# Quad-Thermocouple-Shield.net
KiCad netlist of a schematic drawn in EAGLE
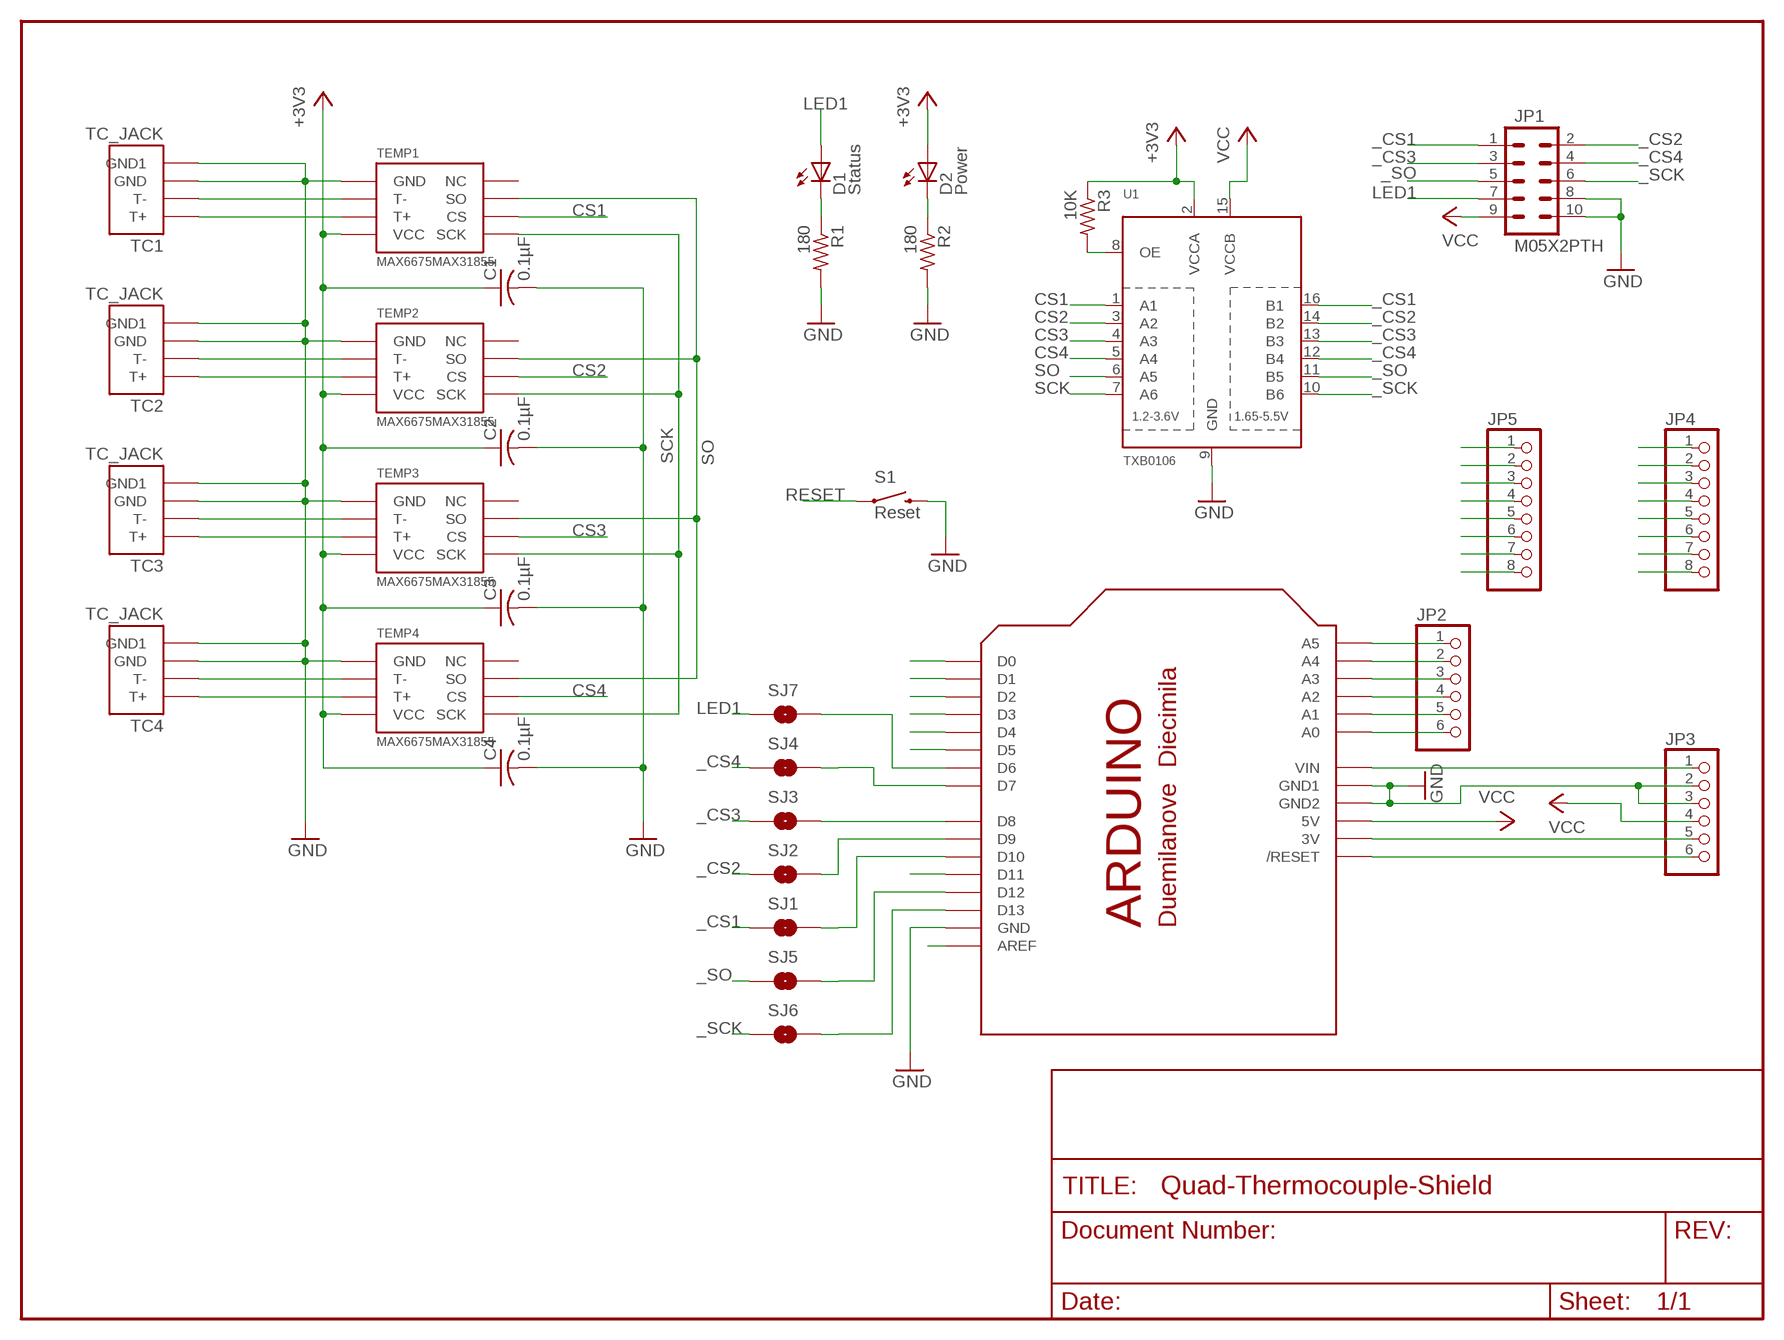
[diagram p0: schematic, sheet 1]

(export (version "E")
  (design (tool "Eeschema 10.0.6"))
  (components
    (comp (ref "C1")
      (value "0.1µF")
      (footprint "eagle-import:C0603")
      (libsource (lib "eagle-import") (part "C-USC0603"))
    )
    (comp (ref "C2")
      (value "0.1µF")
      (footprint "eagle-import:C0603")
      (libsource (lib "eagle-import") (part "C-USC0603"))
    )
    (comp (ref "C3")
      (value "0.1µF")
      (footprint "eagle-import:C0603")
      (libsource (lib "eagle-import") (part "C-USC0603"))
    )
    (comp (ref "C4")
      (value "0.1µF")
      (footprint "eagle-import:C0603")
      (libsource (lib "eagle-import") (part "C-USC0603"))
    )
    (comp (ref "D1")
      (value "Status")
      (footprint "eagle-import:CHIPLED_0805")
      (libsource (lib "eagle-import") (part "LEDCHIPLED_0805"))
    )
    (comp (ref "D2")
      (value "Power")
      (footprint "eagle-import:CHIPLED_0805")
      (libsource (lib "eagle-import") (part "LEDCHIPLED_0805"))
    )
    (comp (ref "JP1")
      (value "M05X2PTH")
      (footprint "eagle-import:AVR_ICSP")
      (libsource (lib "eagle-import") (part "M05X2PTH"))
    )
    (comp (ref "JP2")
      (value "PINHD-1X6CB")
      (footprint "eagle-import:1X06-CLEANBIG")
      (libsource (lib "eagle-import") (part "PINHD-1X6CB"))
    )
    (comp (ref "JP3")
      (value "PINHD-1X6CB")
      (footprint "eagle-import:1X06-CLEANBIG")
      (libsource (lib "eagle-import") (part "PINHD-1X6CB"))
    )
    (comp (ref "JP4")
      (value "PINHD-1X8CLEANBIG")
      (footprint "eagle-import:1X08-CLEANBIG")
      (libsource (lib "eagle-import") (part "PINHD-1X8CLEANBIG"))
    )
    (comp (ref "JP5")
      (value "PINHD-1X8CLEANBIG")
      (footprint "eagle-import:1X08-CLEANBIG")
      (libsource (lib "eagle-import") (part "PINHD-1X8CLEANBIG"))
    )
    (comp (ref "R1")
      (value "180")
      (footprint "eagle-import:R0603")
      (libsource (lib "eagle-import") (part "R-US_R0603"))
    )
    (comp (ref "R2")
      (value "180")
      (footprint "eagle-import:R0603")
      (libsource (lib "eagle-import") (part "R-US_R0603"))
    )
    (comp (ref "R3")
      (value "10K")
      (footprint "eagle-import:R0603")
      (libsource (lib "eagle-import") (part "R-US_R0603"))
    )
    (comp (ref "S1")
      (value "Reset")
      (footprint "eagle-import:TACTILE_SWITCH_SMD")
      (libsource (lib "eagle-import") (part "SWITCH-MOMENTARY-2SMD"))
    )
    (comp (ref "SJ1")
      (value "SOLDERJUMPERTRACE")
      (footprint "eagle-import:SJ_2S-TRACE")
      (libsource (lib "eagle-import") (part "SOLDERJUMPERTRACE"))
    )
    (comp (ref "SJ2")
      (value "SOLDERJUMPERTRACE")
      (footprint "eagle-import:SJ_2S-TRACE")
      (libsource (lib "eagle-import") (part "SOLDERJUMPERTRACE"))
    )
    (comp (ref "SJ3")
      (value "SOLDERJUMPERTRACE")
      (footprint "eagle-import:SJ_2S-TRACE")
      (libsource (lib "eagle-import") (part "SOLDERJUMPERTRACE"))
    )
    (comp (ref "SJ4")
      (value "SOLDERJUMPERTRACE")
      (footprint "eagle-import:SJ_2S-TRACE")
      (libsource (lib "eagle-import") (part "SOLDERJUMPERTRACE"))
    )
    (comp (ref "SJ5")
      (value "SOLDERJUMPERTRACE")
      (footprint "eagle-import:SJ_2S-TRACE")
      (libsource (lib "eagle-import") (part "SOLDERJUMPERTRACE"))
    )
    (comp (ref "SJ6")
      (value "SOLDERJUMPERTRACE")
      (footprint "eagle-import:SJ_2S-TRACE")
      (libsource (lib "eagle-import") (part "SOLDERJUMPERTRACE"))
    )
    (comp (ref "SJ7")
      (value "SOLDERJUMPERTRACE")
      (footprint "eagle-import:SJ_2S-TRACE")
      (libsource (lib "eagle-import") (part "SOLDERJUMPERTRACE"))
    )
    (comp (ref "TC1")
      (value "TC_JACK")
      (footprint "eagle-import:TC_JACK")
      (libsource (lib "eagle-import") (part "TC_JACK"))
    )
    (comp (ref "TC2")
      (value "TC_JACK")
      (footprint "eagle-import:TC_JACK")
      (libsource (lib "eagle-import") (part "TC_JACK"))
    )
    (comp (ref "TC3")
      (value "TC_JACK")
      (footprint "eagle-import:TC_JACK")
      (libsource (lib "eagle-import") (part "TC_JACK"))
    )
    (comp (ref "TC4")
      (value "TC_JACK")
      (footprint "eagle-import:TC_JACK")
      (libsource (lib "eagle-import") (part "TC_JACK"))
    )
    (comp (ref "TEMP1")
      (value "MAX6675MAX31855")
      (footprint "eagle-import:SOIC-8")
      (libsource (lib "eagle-import") (part "MAX6675MAX31855"))
    )
    (comp (ref "TEMP2")
      (value "MAX6675MAX31855")
      (footprint "eagle-import:SOIC-8")
      (libsource (lib "eagle-import") (part "MAX6675MAX31855"))
    )
    (comp (ref "TEMP3")
      (value "MAX6675MAX31855")
      (footprint "eagle-import:SOIC-8")
      (libsource (lib "eagle-import") (part "MAX6675MAX31855"))
    )
    (comp (ref "TEMP4")
      (value "MAX6675MAX31855")
      (footprint "eagle-import:SOIC-8")
      (libsource (lib "eagle-import") (part "MAX6675MAX31855"))
    )
    (comp (ref "U$3")
      (value "ARDUINOUNO")
      (footprint "eagle-import:ARDUINO")
      (libsource (lib "eagle-import") (part "ARDUINOUNO"))
    )
    (comp (ref "U1")
      (value "TXB0106")
      (footprint "eagle-import:TSSOP16")
      (libsource (lib "eagle-import") (part "TXB0106PWR"))
    )
  )
  (nets
    (net (code "1") (name "+3V3") (class "Default")
      (node (ref "C1") (pin "1") (pinfunction "1_1") (pintype "passive"))
      (node (ref "C2") (pin "1") (pinfunction "1_1") (pintype "passive"))
      (node (ref "C3") (pin "1") (pinfunction "1_1") (pintype "passive"))
      (node (ref "C4") (pin "1") (pinfunction "1_1") (pintype "passive"))
      (node (ref "D2") (pin "A") (pinfunction "A_A") (pintype "passive"))
      (node (ref "JP3") (pin "5") (pinfunction "5_5") (pintype "passive"))
      (node (ref "R3") (pin "1") (pinfunction "1_1") (pintype "passive"))
      (node (ref "TEMP1") (pin "VCC") (pinfunction "VCC_VCC") (pintype "bidirectional"))
      (node (ref "TEMP2") (pin "VCC") (pinfunction "VCC_VCC") (pintype "bidirectional"))
      (node (ref "TEMP3") (pin "VCC") (pinfunction "VCC_VCC") (pintype "bidirectional"))
      (node (ref "TEMP4") (pin "VCC") (pinfunction "VCC_VCC") (pintype "bidirectional"))
      (node (ref "U$3") (pin "3V") (pinfunction "3V_3V") (pintype "power_in"))
      (node (ref "U1") (pin "2") (pinfunction "VCCA_2") (pintype "bidirectional"))
    )
    (net (code "2") (name "/AREF") (class "Default")
      (node (ref "JP4") (pin "8") (pinfunction "8_8") (pintype "passive"))
      (node (ref "U$3") (pin "AREF") (pinfunction "AREF_AREF") (pintype "bidirectional"))
    )
    (net (code "3") (name "/CS1") (class "Default")
      (node (ref "TEMP1") (pin "CS") (pinfunction "CS_CS") (pintype "bidirectional"))
      (node (ref "U1") (pin "1") (pinfunction "A1_1") (pintype "bidirectional"))
    )
    (net (code "4") (name "/CS2") (class "Default")
      (node (ref "TEMP2") (pin "CS") (pinfunction "CS_CS") (pintype "bidirectional"))
      (node (ref "U1") (pin "3") (pinfunction "A2_3") (pintype "bidirectional"))
    )
    (net (code "5") (name "/CS3") (class "Default")
      (node (ref "TEMP3") (pin "CS") (pinfunction "CS_CS") (pintype "bidirectional"))
      (node (ref "U1") (pin "4") (pinfunction "A3_4") (pintype "bidirectional"))
    )
    (net (code "6") (name "/CS4") (class "Default")
      (node (ref "TEMP4") (pin "CS") (pinfunction "CS_CS") (pintype "bidirectional"))
      (node (ref "U1") (pin "5") (pinfunction "A4_5") (pintype "bidirectional"))
    )
    (net (code "7") (name "/D0") (class "Default")
      (node (ref "JP5") (pin "1") (pinfunction "1_1") (pintype "passive"))
      (node (ref "U$3") (pin "D0") (pinfunction "D0_D0") (pintype "bidirectional"))
    )
    (net (code "8") (name "/D1") (class "Default")
      (node (ref "JP5") (pin "2") (pinfunction "2_2") (pintype "passive"))
      (node (ref "U$3") (pin "D1") (pinfunction "D1_D1") (pintype "bidirectional"))
    )
    (net (code "9") (name "/D2") (class "Default")
      (node (ref "JP5") (pin "3") (pinfunction "3_3") (pintype "passive"))
      (node (ref "U$3") (pin "D2") (pinfunction "D2_D2") (pintype "bidirectional"))
    )
    (net (code "10") (name "/D3") (class "Default")
      (node (ref "JP5") (pin "4") (pinfunction "4_4") (pintype "passive"))
      (node (ref "U$3") (pin "D3") (pinfunction "D3_D3") (pintype "bidirectional"))
    )
    (net (code "11") (name "/D4") (class "Default")
      (node (ref "JP5") (pin "5") (pinfunction "5_5") (pintype "passive"))
      (node (ref "U$3") (pin "D4") (pinfunction "D4_D4") (pintype "bidirectional"))
    )
    (net (code "12") (name "/D5") (class "Default")
      (node (ref "JP5") (pin "6") (pinfunction "6_6") (pintype "passive"))
      (node (ref "U$3") (pin "D5") (pinfunction "D5_D5") (pintype "bidirectional"))
    )
    (net (code "13") (name "/D6") (class "Default")
      (node (ref "JP5") (pin "7") (pinfunction "7_7") (pintype "passive"))
      (node (ref "SJ7") (pin "2") (pinfunction "2_2") (pintype "passive"))
      (node (ref "U$3") (pin "D6") (pinfunction "D6_D6") (pintype "bidirectional"))
    )
    (net (code "14") (name "/D7") (class "Default")
      (node (ref "JP5") (pin "8") (pinfunction "8_8") (pintype "passive"))
      (node (ref "SJ4") (pin "2") (pinfunction "2_2") (pintype "passive"))
      (node (ref "U$3") (pin "D7") (pinfunction "D7_D7") (pintype "bidirectional"))
    )
    (net (code "15") (name "/D8") (class "Default")
      (node (ref "JP4") (pin "1") (pinfunction "1_1") (pintype "passive"))
      (node (ref "SJ3") (pin "2") (pinfunction "2_2") (pintype "passive"))
      (node (ref "U$3") (pin "D8") (pinfunction "D8_D8") (pintype "bidirectional"))
    )
    (net (code "16") (name "/D9") (class "Default")
      (node (ref "JP4") (pin "2") (pinfunction "2_2") (pintype "passive"))
      (node (ref "SJ2") (pin "2") (pinfunction "2_2") (pintype "passive"))
      (node (ref "U$3") (pin "D9") (pinfunction "D9_D9") (pintype "bidirectional"))
    )
    (net (code "17") (name "/D10") (class "Default")
      (node (ref "JP4") (pin "3") (pinfunction "3_3") (pintype "passive"))
      (node (ref "SJ1") (pin "2") (pinfunction "2_2") (pintype "passive"))
      (node (ref "U$3") (pin "D10") (pinfunction "D10_D10") (pintype "bidirectional"))
    )
    (net (code "18") (name "/D11") (class "Default")
      (node (ref "JP4") (pin "4") (pinfunction "4_4") (pintype "passive"))
      (node (ref "U$3") (pin "D11") (pinfunction "D11_D11") (pintype "bidirectional"))
    )
    (net (code "19") (name "/D12") (class "Default")
      (node (ref "JP4") (pin "5") (pinfunction "5_5") (pintype "passive"))
      (node (ref "SJ5") (pin "2") (pinfunction "2_2") (pintype "passive"))
      (node (ref "U$3") (pin "D12") (pinfunction "D12_D12") (pintype "bidirectional"))
    )
    (net (code "20") (name "/D13") (class "Default")
      (node (ref "JP4") (pin "6") (pinfunction "6_6") (pintype "passive"))
      (node (ref "SJ6") (pin "2") (pinfunction "2_2") (pintype "passive"))
      (node (ref "U$3") (pin "D13") (pinfunction "D13_D13") (pintype "bidirectional"))
    )
    (net (code "21") (name "/LED1") (class "Default")
      (node (ref "D1") (pin "A") (pinfunction "A_A") (pintype "passive"))
      (node (ref "JP1") (pin "7") (pinfunction "7_7") (pintype "passive"))
      (node (ref "SJ7") (pin "1") (pinfunction "1_1") (pintype "passive"))
    )
    (net (code "22") (name "/RESET") (class "Default")
      (node (ref "JP3") (pin "6") (pinfunction "6_6") (pintype "passive"))
      (node (ref "S1") (pin "1") (pinfunction "1_1") (pintype "passive"))
      (node (ref "U$3") (pin "RESET") (pinfunction "/RESET_RESET") (pintype "bidirectional"))
    )
    (net (code "23") (name "/SCK") (class "Default")
      (node (ref "TEMP1") (pin "SCK") (pinfunction "SCK_SCK") (pintype "bidirectional"))
      (node (ref "TEMP2") (pin "SCK") (pinfunction "SCK_SCK") (pintype "bidirectional"))
      (node (ref "TEMP3") (pin "SCK") (pinfunction "SCK_SCK") (pintype "bidirectional"))
      (node (ref "TEMP4") (pin "SCK") (pinfunction "SCK_SCK") (pintype "bidirectional"))
      (node (ref "U1") (pin "7") (pinfunction "A6_7") (pintype "bidirectional"))
    )
    (net (code "24") (name "/SO") (class "Default")
      (node (ref "TEMP1") (pin "SO") (pinfunction "SO_SO") (pintype "bidirectional"))
      (node (ref "TEMP2") (pin "SO") (pinfunction "SO_SO") (pintype "bidirectional"))
      (node (ref "TEMP3") (pin "SO") (pinfunction "SO_SO") (pintype "bidirectional"))
      (node (ref "TEMP4") (pin "SO") (pinfunction "SO_SO") (pintype "bidirectional"))
      (node (ref "U1") (pin "6") (pinfunction "A5_6") (pintype "bidirectional"))
    )
    (net (code "25") (name "/_CS1") (class "Default")
      (node (ref "JP1") (pin "1") (pinfunction "1_1") (pintype "passive"))
      (node (ref "SJ1") (pin "1") (pinfunction "1_1") (pintype "passive"))
      (node (ref "U1") (pin "16") (pinfunction "B1_16") (pintype "bidirectional"))
    )
    (net (code "26") (name "/_CS2") (class "Default")
      (node (ref "JP1") (pin "2") (pinfunction "2_2") (pintype "passive"))
      (node (ref "SJ2") (pin "1") (pinfunction "1_1") (pintype "passive"))
      (node (ref "U1") (pin "14") (pinfunction "B2_14") (pintype "bidirectional"))
    )
    (net (code "27") (name "/_CS3") (class "Default")
      (node (ref "JP1") (pin "3") (pinfunction "3_3") (pintype "passive"))
      (node (ref "SJ3") (pin "1") (pinfunction "1_1") (pintype "passive"))
      (node (ref "U1") (pin "13") (pinfunction "B3_13") (pintype "bidirectional"))
    )
    (net (code "28") (name "/_CS4") (class "Default")
      (node (ref "JP1") (pin "4") (pinfunction "4_4") (pintype "passive"))
      (node (ref "SJ4") (pin "1") (pinfunction "1_1") (pintype "passive"))
      (node (ref "U1") (pin "12") (pinfunction "B4_12") (pintype "bidirectional"))
    )
    (net (code "29") (name "/_SCK") (class "Default")
      (node (ref "JP1") (pin "6") (pinfunction "6_6") (pintype "passive"))
      (node (ref "SJ6") (pin "1") (pinfunction "1_1") (pintype "passive"))
      (node (ref "U1") (pin "10") (pinfunction "B6_10") (pintype "bidirectional"))
    )
    (net (code "30") (name "/_SO") (class "Default")
      (node (ref "JP1") (pin "5") (pinfunction "5_5") (pintype "passive"))
      (node (ref "SJ5") (pin "1") (pinfunction "1_1") (pintype "passive"))
      (node (ref "U1") (pin "11") (pinfunction "B5_11") (pintype "bidirectional"))
    )
    (net (code "31") (name "GND") (class "Default")
      (node (ref "C1") (pin "2") (pinfunction "2_2") (pintype "passive"))
      (node (ref "C2") (pin "2") (pinfunction "2_2") (pintype "passive"))
      (node (ref "C3") (pin "2") (pinfunction "2_2") (pintype "passive"))
      (node (ref "C4") (pin "2") (pinfunction "2_2") (pintype "passive"))
      (node (ref "JP1") (pin "10") (pinfunction "10_10") (pintype "passive"))
      (node (ref "JP1") (pin "8") (pinfunction "8_8") (pintype "passive"))
      (node (ref "JP3") (pin "2") (pinfunction "2_2") (pintype "passive"))
      (node (ref "JP3") (pin "3") (pinfunction "3_3") (pintype "passive"))
      (node (ref "JP4") (pin "7") (pinfunction "7_7") (pintype "passive"))
      (node (ref "R1") (pin "2") (pinfunction "2_2") (pintype "passive"))
      (node (ref "R2") (pin "2") (pinfunction "2_2") (pintype "passive"))
      (node (ref "S1") (pin "3") (pinfunction "2_3") (pintype "passive"))
      (node (ref "TC1") (pin "P$1") (pinfunction "GND_P$1") (pintype "bidirectional"))
      (node (ref "TC1") (pin "P$2") (pinfunction "GND1_P$2") (pintype "bidirectional"))
      (node (ref "TC2") (pin "P$1") (pinfunction "GND_P$1") (pintype "bidirectional"))
      (node (ref "TC2") (pin "P$2") (pinfunction "GND1_P$2") (pintype "bidirectional"))
      (node (ref "TC3") (pin "P$1") (pinfunction "GND_P$1") (pintype "bidirectional"))
      (node (ref "TC3") (pin "P$2") (pinfunction "GND1_P$2") (pintype "bidirectional"))
      (node (ref "TC4") (pin "P$1") (pinfunction "GND_P$1") (pintype "bidirectional"))
      (node (ref "TC4") (pin "P$2") (pinfunction "GND1_P$2") (pintype "bidirectional"))
      (node (ref "TEMP1") (pin "GND") (pinfunction "GND_GND") (pintype "bidirectional"))
      (node (ref "TEMP2") (pin "GND") (pinfunction "GND_GND") (pintype "bidirectional"))
      (node (ref "TEMP3") (pin "GND") (pinfunction "GND_GND") (pintype "bidirectional"))
      (node (ref "TEMP4") (pin "GND") (pinfunction "GND_GND") (pintype "bidirectional"))
      (node (ref "U$3") (pin "GND") (pinfunction "GND_GND") (pintype "power_in"))
      (node (ref "U$3") (pin "GND1") (pinfunction "GND1_GND1") (pintype "power_in"))
      (node (ref "U$3") (pin "GND2") (pinfunction "GND2_GND2") (pintype "power_in"))
      (node (ref "U1") (pin "9") (pinfunction "GND_9") (pintype "bidirectional"))
    )
    (net (code "32") (name "Net-(D1-PadC)") (class "Default")
      (node (ref "D1") (pin "C") (pinfunction "C_C") (pintype "passive"))
      (node (ref "R1") (pin "1") (pinfunction "1_1") (pintype "passive"))
    )
    (net (code "33") (name "Net-(D2-PadC)") (class "Default")
      (node (ref "D2") (pin "C") (pinfunction "C_C") (pintype "passive"))
      (node (ref "R2") (pin "1") (pinfunction "1_1") (pintype "passive"))
    )
    (net (code "34") (name "Net-(JP2-Pad1)") (class "Default")
      (node (ref "JP2") (pin "1") (pinfunction "1_1") (pintype "passive"))
      (node (ref "U$3") (pin "A5") (pinfunction "A5_A5") (pintype "bidirectional"))
    )
    (net (code "35") (name "Net-(JP2-Pad2)") (class "Default")
      (node (ref "JP2") (pin "2") (pinfunction "2_2") (pintype "passive"))
      (node (ref "U$3") (pin "A4") (pinfunction "A4_A4") (pintype "bidirectional"))
    )
    (net (code "36") (name "Net-(JP2-Pad3)") (class "Default")
      (node (ref "JP2") (pin "3") (pinfunction "3_3") (pintype "passive"))
      (node (ref "U$3") (pin "A3") (pinfunction "A3_A3") (pintype "bidirectional"))
    )
    (net (code "37") (name "Net-(JP2-Pad4)") (class "Default")
      (node (ref "JP2") (pin "4") (pinfunction "4_4") (pintype "passive"))
      (node (ref "U$3") (pin "A2") (pinfunction "A2_A2") (pintype "bidirectional"))
    )
    (net (code "38") (name "Net-(JP2-Pad5)") (class "Default")
      (node (ref "JP2") (pin "5") (pinfunction "5_5") (pintype "passive"))
      (node (ref "U$3") (pin "A1") (pinfunction "A1_A1") (pintype "bidirectional"))
    )
    (net (code "39") (name "Net-(JP2-Pad6)") (class "Default")
      (node (ref "JP2") (pin "6") (pinfunction "6_6") (pintype "passive"))
      (node (ref "U$3") (pin "A0") (pinfunction "A0_A0") (pintype "bidirectional"))
    )
    (net (code "40") (name "Net-(JP3-Pad1)") (class "Default")
      (node (ref "JP3") (pin "1") (pinfunction "1_1") (pintype "passive"))
      (node (ref "U$3") (pin "VIN") (pinfunction "VIN_VIN") (pintype "power_in"))
    )
    (net (code "41") (name "Net-(TC1-PadT+)") (class "Default")
      (node (ref "TC1") (pin "T+") (pinfunction "T+_T+") (pintype "bidirectional"))
      (node (ref "TEMP1") (pin "T+") (pinfunction "T+_T+") (pintype "bidirectional"))
    )
    (net (code "42") (name "Net-(TC1-PadT-)") (class "Default")
      (node (ref "TC1") (pin "T-") (pinfunction "T-_T-") (pintype "bidirectional"))
      (node (ref "TEMP1") (pin "T-") (pinfunction "T-_T-") (pintype "bidirectional"))
    )
    (net (code "43") (name "Net-(TC2-PadT+)") (class "Default")
      (node (ref "TC2") (pin "T+") (pinfunction "T+_T+") (pintype "bidirectional"))
      (node (ref "TEMP2") (pin "T+") (pinfunction "T+_T+") (pintype "bidirectional"))
    )
    (net (code "44") (name "Net-(TC2-PadT-)") (class "Default")
      (node (ref "TC2") (pin "T-") (pinfunction "T-_T-") (pintype "bidirectional"))
      (node (ref "TEMP2") (pin "T-") (pinfunction "T-_T-") (pintype "bidirectional"))
    )
    (net (code "45") (name "Net-(TC3-PadT+)") (class "Default")
      (node (ref "TC3") (pin "T+") (pinfunction "T+_T+") (pintype "bidirectional"))
      (node (ref "TEMP3") (pin "T+") (pinfunction "T+_T+") (pintype "bidirectional"))
    )
    (net (code "46") (name "Net-(TC3-PadT-)") (class "Default")
      (node (ref "TC3") (pin "T-") (pinfunction "T-_T-") (pintype "bidirectional"))
      (node (ref "TEMP3") (pin "T-") (pinfunction "T-_T-") (pintype "bidirectional"))
    )
    (net (code "47") (name "Net-(TC4-PadT+)") (class "Default")
      (node (ref "TC4") (pin "T+") (pinfunction "T+_T+") (pintype "bidirectional"))
      (node (ref "TEMP4") (pin "T+") (pinfunction "T+_T+") (pintype "bidirectional"))
    )
    (net (code "48") (name "Net-(TC4-PadT-)") (class "Default")
      (node (ref "TC4") (pin "T-") (pinfunction "T-_T-") (pintype "bidirectional"))
      (node (ref "TEMP4") (pin "T-") (pinfunction "T-_T-") (pintype "bidirectional"))
    )
    (net (code "49") (name "Net-(U1-OE)") (class "Default")
      (node (ref "R3") (pin "2") (pinfunction "2_2") (pintype "passive"))
      (node (ref "U1") (pin "8") (pinfunction "OE_8") (pintype "bidirectional"))
    )
    (net (code "50") (name "VCC") (class "Default")
      (node (ref "JP1") (pin "9") (pinfunction "9_9") (pintype "passive"))
      (node (ref "JP3") (pin "4") (pinfunction "4_4") (pintype "passive"))
      (node (ref "U$3") (pin "5V") (pinfunction "5V_5V") (pintype "power_in"))
      (node (ref "U1") (pin "15") (pinfunction "VCCB_15") (pintype "bidirectional"))
    )
    (net (code "51") (name "unconnected-(TEMP1-PadNC)") (class "Default")
      (node (ref "TEMP1") (pin "NC") (pinfunction "NC_NC") (pintype "no_connect"))
    )
    (net (code "52") (name "unconnected-(TEMP2-PadNC)") (class "Default")
      (node (ref "TEMP2") (pin "NC") (pinfunction "NC_NC") (pintype "no_connect"))
    )
    (net (code "53") (name "unconnected-(TEMP3-PadNC)") (class "Default")
      (node (ref "TEMP3") (pin "NC") (pinfunction "NC_NC") (pintype "no_connect"))
    )
    (net (code "54") (name "unconnected-(TEMP4-PadNC)") (class "Default")
      (node (ref "TEMP4") (pin "NC") (pinfunction "NC_NC") (pintype "no_connect"))
    )
  )
)
